# SiP.net
KiCad netlist of a schematic drawn in Altium Designer
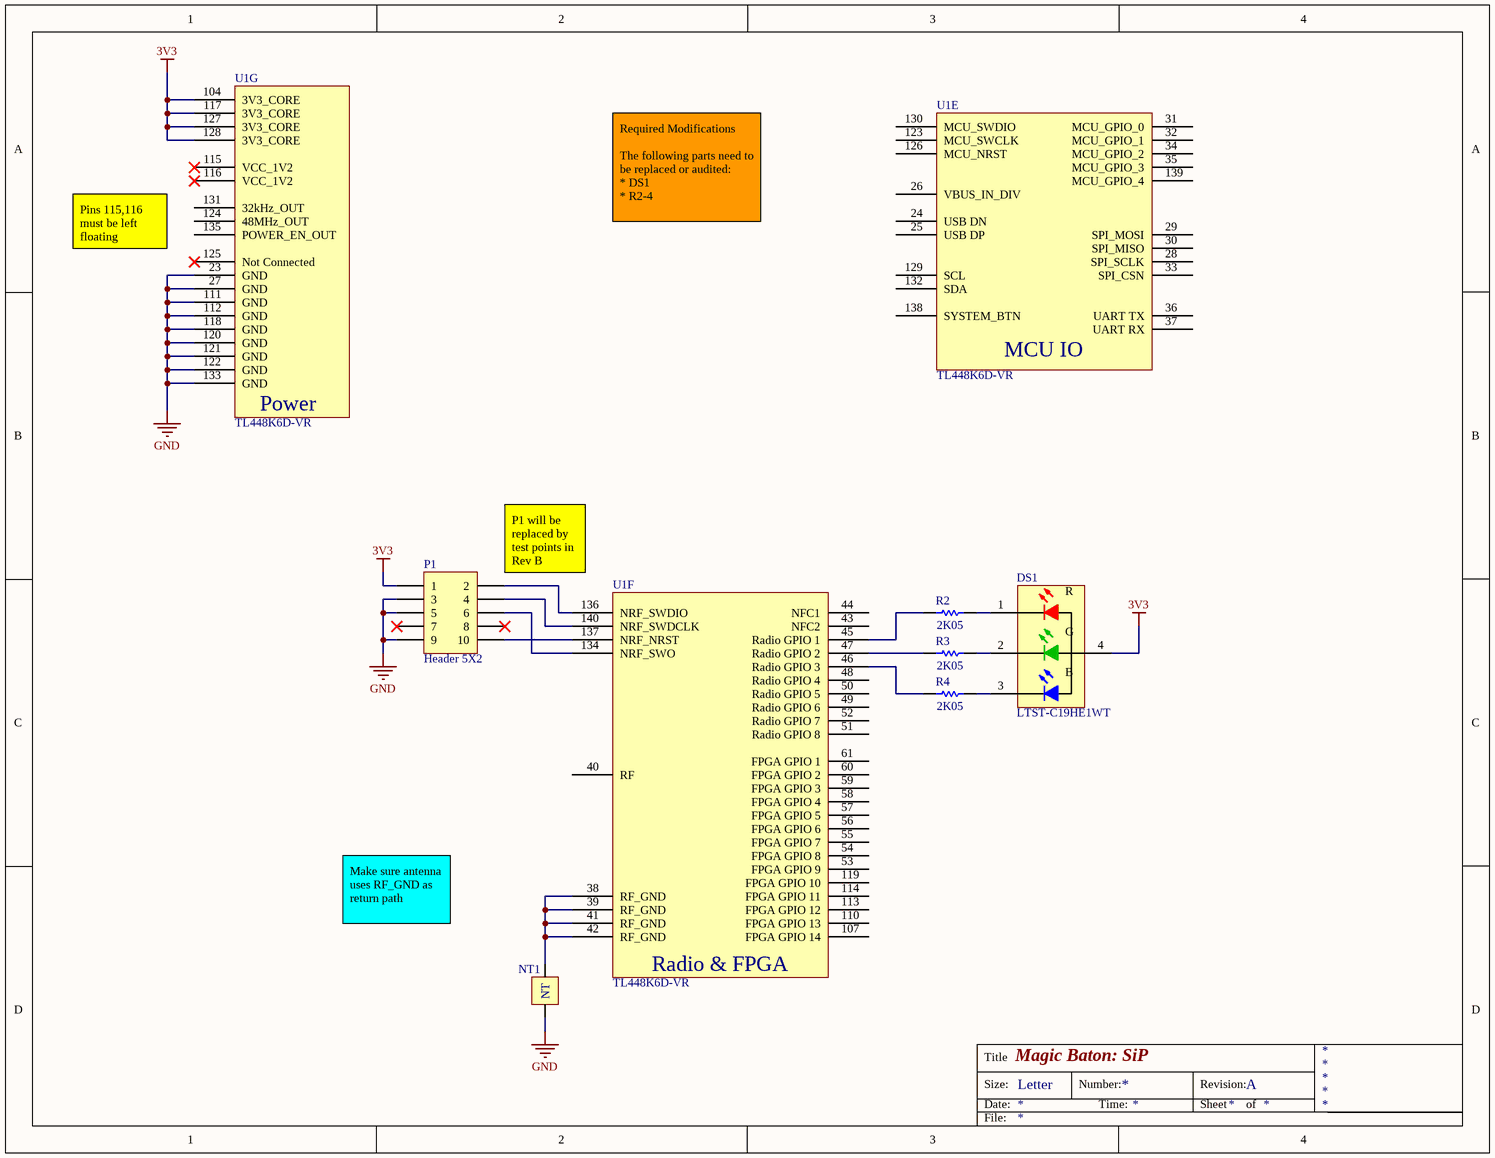
[diagram p0: SiP.SchDoc]

(export (version "E")
  (design (tool "Eeschema 10.0.6"))
  (components
    (comp (ref "DS1")
      (value "LTST-C19HE1WT")
      (footprint "LTST-C19HE1WT-4_V")
      (description "LED Tri-Color Blue/Green/Red, 5 V, -20 to 80 degC, 4-Pin SMD, RoHS, Tape and Reel")
      (fields (field (name "MANUFACTURER") "Lite-On"))
      (libsource (lib "Altium Content Vault") (part "LTST-C19HE1WT-4"))
    )
    (comp (ref "NT1") (value "NT1") (description "Nettie") (libsource (lib "CustomParts") (part "NT1")))
    (comp (ref "P1")
      (value "Header 5X2")
      (footprint "HDR2X5")
      (description "Header, 5-Pin, Dual row")
      (fields (field (name "PUBLISHER") "Altium Limited"))
      (libsource (lib "Miscellaneous Connectors") (part "Header 5X2"))
    )
    (comp (ref "R2")
      (value "2K05")
      (footprint "AXIAL-0.3")
      (description "Resistor")
      (fields (field (name "Comment") "Res1") (field (name "PUBLISHER") "Altium Limited"))
      (libsource (lib "Miscellaneous Devices") (part "Res1"))
    )
    (comp (ref "R3")
      (value "2K05")
      (footprint "AXIAL-0.3")
      (description "Resistor")
      (fields (field (name "Comment") "Res1") (field (name "PUBLISHER") "Altium Limited"))
      (libsource (lib "Miscellaneous Devices") (part "Res1"))
    )
    (comp (ref "R4")
      (value "2K05")
      (footprint "AXIAL-0.3")
      (description "Resistor")
      (fields (field (name "Comment") "Res1") (field (name "PUBLISHER") "Altium Limited"))
      (libsource (lib "Miscellaneous Devices") (part "Res1"))
    )
    (comp (ref "U1")
      (value "TL448K6D-VR")
      (footprint "WatchmanModule_v4")
      (libsource (lib "TL448K6D-VR_library_rev1p2") (part "TL448K6D-VR"))
    )
  )
  (nets
    (net (code "1") (name "3V3") (class "Default")
      (node (ref "DS1") (pin "4") (pinfunction "A_4") (pintype "passive"))
      (node (ref "P1") (pin "1") (pinfunction "1_1") (pintype "passive"))
      (node (ref "U1") (pin "104") (pinfunction "3V3_CORE_104") (pintype "passive"))
      (node (ref "U1") (pin "117") (pinfunction "3V3_CORE_117") (pintype "passive"))
      (node (ref "U1") (pin "127") (pinfunction "3V3_CORE_127") (pintype "passive"))
      (node (ref "U1") (pin "128") (pinfunction "3V3_CORE_128") (pintype "passive"))
    )
    (net (code "2") (name "GND") (class "Default")
      (node (ref "NT1") (pin "1") (pinfunction "1_1") (pintype "passive"))
      (node (ref "P1") (pin "3") (pinfunction "3_3") (pintype "passive"))
      (node (ref "P1") (pin "5") (pinfunction "5_5") (pintype "passive"))
      (node (ref "P1") (pin "9") (pinfunction "9_9") (pintype "passive"))
      (node (ref "U1") (pin "111") (pinfunction "GND_111") (pintype "passive"))
      (node (ref "U1") (pin "112") (pinfunction "GND_112") (pintype "passive"))
      (node (ref "U1") (pin "118") (pinfunction "GND_118") (pintype "passive"))
      (node (ref "U1") (pin "120") (pinfunction "GND_120") (pintype "passive"))
      (node (ref "U1") (pin "121") (pinfunction "GND_121") (pintype "passive"))
      (node (ref "U1") (pin "122") (pinfunction "GND_122") (pintype "passive"))
      (node (ref "U1") (pin "133") (pinfunction "GND_133") (pintype "passive"))
      (node (ref "U1") (pin "23") (pinfunction "GND_23") (pintype "passive"))
      (node (ref "U1") (pin "27") (pinfunction "GND_27") (pintype "passive"))
    )
    (net (code "3") (name "Net-(DS1-B)") (class "Default")
      (node (ref "DS1") (pin "3") (pinfunction "B_3") (pintype "passive"))
      (node (ref "R4") (pin "2") (pinfunction "2_2") (pintype "passive"))
    )
    (net (code "4") (name "Net-(DS1-G)") (class "Default")
      (node (ref "DS1") (pin "2") (pinfunction "G_2") (pintype "passive"))
      (node (ref "R3") (pin "2") (pinfunction "2_2") (pintype "passive"))
    )
    (net (code "5") (name "Net-(DS1-R)") (class "Default")
      (node (ref "DS1") (pin "1") (pinfunction "R_1") (pintype "passive"))
      (node (ref "R2") (pin "2") (pinfunction "2_2") (pintype "passive"))
    )
    (net (code "6") (name "Net-(NT1-Pad2)") (class "Default")
      (node (ref "NT1") (pin "2") (pinfunction "2_2") (pintype "passive"))
      (node (ref "U1") (pin "38") (pinfunction "RF_GND_38") (pintype "passive"))
      (node (ref "U1") (pin "39") (pinfunction "RF_GND_39") (pintype "passive"))
      (node (ref "U1") (pin "41") (pinfunction "RF_GND_41") (pintype "passive"))
      (node (ref "U1") (pin "42") (pinfunction "RF_GND_42") (pintype "passive"))
    )
    (net (code "7") (name "Net-(U1F-NRF_NRST)") (class "Default")
      (node (ref "P1") (pin "10") (pinfunction "10_10") (pintype "passive"))
      (node (ref "U1") (pin "137") (pinfunction "NRF_NRST_137") (pintype "passive"))
    )
    (net (code "8") (name "Net-(U1F-NRF_SWDCLK)") (class "Default")
      (node (ref "P1") (pin "4") (pinfunction "4_4") (pintype "passive"))
      (node (ref "U1") (pin "140") (pinfunction "NRF_SWDCLK_140") (pintype "passive"))
    )
    (net (code "9") (name "Net-(U1F-NRF_SWDIO)") (class "Default")
      (node (ref "P1") (pin "2") (pinfunction "2_2") (pintype "passive"))
      (node (ref "U1") (pin "136") (pinfunction "NRF_SWDIO_136") (pintype "passive"))
    )
    (net (code "10") (name "Net-(U1F-NRF_SWO)") (class "Default")
      (node (ref "P1") (pin "6") (pinfunction "6_6") (pintype "passive"))
      (node (ref "U1") (pin "134") (pinfunction "NRF_SWO_134") (pintype "passive"))
    )
    (net (code "11") (name "Net-(U1F-Radio_GPIO_1)") (class "Default")
      (node (ref "R2") (pin "1") (pinfunction "1_1") (pintype "passive"))
      (node (ref "U1") (pin "45") (pinfunction "Radio_GPIO_1_45") (pintype "passive"))
    )
    (net (code "12") (name "Net-(U1F-Radio_GPIO_2)") (class "Default")
      (node (ref "R3") (pin "1") (pinfunction "1_1") (pintype "passive"))
      (node (ref "U1") (pin "47") (pinfunction "Radio_GPIO_2_47") (pintype "passive"))
    )
    (net (code "13") (name "Net-(U1F-Radio_GPIO_3)") (class "Default")
      (node (ref "R4") (pin "1") (pinfunction "1_1") (pintype "passive"))
      (node (ref "U1") (pin "46") (pinfunction "Radio_GPIO_3_46") (pintype "passive"))
    )
    (net (code "14") (name "unconnected-(P1-Pad7)") (class "Default")
      (node (ref "P1") (pin "7") (pinfunction "7_7") (pintype "passive+no_connect"))
    )
    (net (code "15") (name "unconnected-(P1-Pad8)") (class "Default")
      (node (ref "P1") (pin "8") (pinfunction "8_8") (pintype "passive+no_connect"))
    )
    (net (code "16") (name "unconnected-(U1E-MCU_GPIO_0-Pad31)") (class "Default")
      (node (ref "U1") (pin "31") (pinfunction "MCU_GPIO_0_31") (pintype "passive"))
    )
    (net (code "17") (name "unconnected-(U1E-MCU_GPIO_1-Pad32)") (class "Default")
      (node (ref "U1") (pin "32") (pinfunction "MCU_GPIO_1_32") (pintype "passive"))
    )
    (net (code "18") (name "unconnected-(U1E-MCU_GPIO_2-Pad34)") (class "Default")
      (node (ref "U1") (pin "34") (pinfunction "MCU_GPIO_2_34") (pintype "passive"))
    )
    (net (code "19") (name "unconnected-(U1E-MCU_GPIO_3-Pad35)") (class "Default")
      (node (ref "U1") (pin "35") (pinfunction "MCU_GPIO_3_35") (pintype "passive"))
    )
    (net (code "20") (name "unconnected-(U1E-MCU_GPIO_4-Pad139)") (class "Default")
      (node (ref "U1") (pin "139") (pinfunction "MCU_GPIO_4_139") (pintype "passive"))
    )
    (net (code "21") (name "unconnected-(U1E-MCU_NRST-Pad126)") (class "Default")
      (node (ref "U1") (pin "126") (pinfunction "MCU_NRST_126") (pintype "passive"))
    )
    (net (code "22") (name "unconnected-(U1E-MCU_SWCLK-Pad123)") (class "Default")
      (node (ref "U1") (pin "123") (pinfunction "MCU_SWCLK_123") (pintype "passive"))
    )
    (net (code "23") (name "unconnected-(U1E-MCU_SWDIO-Pad130)") (class "Default")
      (node (ref "U1") (pin "130") (pinfunction "MCU_SWDIO_130") (pintype "passive"))
    )
    (net (code "24") (name "unconnected-(U1E-SCL-Pad129)") (class "Default")
      (node (ref "U1") (pin "129") (pinfunction "SCL_129") (pintype "passive"))
    )
    (net (code "25") (name "unconnected-(U1E-SDA-Pad132)") (class "Default")
      (node (ref "U1") (pin "132") (pinfunction "SDA_132") (pintype "passive"))
    )
    (net (code "26") (name "unconnected-(U1E-SPI_CSN-Pad33)") (class "Default")
      (node (ref "U1") (pin "33") (pinfunction "SPI_CSN_33") (pintype "passive"))
    )
    (net (code "27") (name "unconnected-(U1E-SPI_MISO-Pad30)") (class "Default")
      (node (ref "U1") (pin "30") (pinfunction "SPI_MISO_30") (pintype "passive"))
    )
    (net (code "28") (name "unconnected-(U1E-SPI_MOSI-Pad29)") (class "Default")
      (node (ref "U1") (pin "29") (pinfunction "SPI_MOSI_29") (pintype "passive"))
    )
    (net (code "29") (name "unconnected-(U1E-SPI_SCLK-Pad28)") (class "Default")
      (node (ref "U1") (pin "28") (pinfunction "SPI_SCLK_28") (pintype "passive"))
    )
    (net (code "30") (name "unconnected-(U1E-SYSTEM_BTN-Pad138)") (class "Default")
      (node (ref "U1") (pin "138") (pinfunction "SYSTEM_BTN_138") (pintype "passive"))
    )
    (net (code "31") (name "unconnected-(U1E-UART_RX-Pad37)") (class "Default")
      (node (ref "U1") (pin "37") (pinfunction "UART_RX_37") (pintype "passive"))
    )
    (net (code "32") (name "unconnected-(U1E-UART_TX-Pad36)") (class "Default")
      (node (ref "U1") (pin "36") (pinfunction "UART_TX_36") (pintype "passive"))
    )
    (net (code "33") (name "unconnected-(U1E-USB_DN-Pad24)") (class "Default")
      (node (ref "U1") (pin "24") (pinfunction "USB_DN_24") (pintype "passive"))
    )
    (net (code "34") (name "unconnected-(U1E-USB_DP-Pad25)") (class "Default")
      (node (ref "U1") (pin "25") (pinfunction "USB_DP_25") (pintype "passive"))
    )
    (net (code "35") (name "unconnected-(U1E-VBUS_IN_DIV-Pad26)") (class "Default")
      (node (ref "U1") (pin "26") (pinfunction "VBUS_IN_DIV_26") (pintype "passive"))
    )
    (net (code "36") (name "unconnected-(U1F-FPGA_GPIO_1-Pad61)") (class "Default")
      (node (ref "U1") (pin "61") (pinfunction "FPGA_GPIO_1_61") (pintype "passive"))
    )
    (net (code "37") (name "unconnected-(U1F-FPGA_GPIO_2-Pad60)") (class "Default")
      (node (ref "U1") (pin "60") (pinfunction "FPGA_GPIO_2_60") (pintype "passive"))
    )
    (net (code "38") (name "unconnected-(U1F-FPGA_GPIO_3-Pad59)") (class "Default")
      (node (ref "U1") (pin "59") (pinfunction "FPGA_GPIO_3_59") (pintype "passive"))
    )
    (net (code "39") (name "unconnected-(U1F-FPGA_GPIO_4-Pad58)") (class "Default")
      (node (ref "U1") (pin "58") (pinfunction "FPGA_GPIO_4_58") (pintype "passive"))
    )
    (net (code "40") (name "unconnected-(U1F-FPGA_GPIO_5-Pad57)") (class "Default")
      (node (ref "U1") (pin "57") (pinfunction "FPGA_GPIO_5_57") (pintype "passive"))
    )
    (net (code "41") (name "unconnected-(U1F-FPGA_GPIO_6-Pad56)") (class "Default")
      (node (ref "U1") (pin "56") (pinfunction "FPGA_GPIO_6_56") (pintype "passive"))
    )
    (net (code "42") (name "unconnected-(U1F-FPGA_GPIO_7-Pad55)") (class "Default")
      (node (ref "U1") (pin "55") (pinfunction "FPGA_GPIO_7_55") (pintype "passive"))
    )
    (net (code "43") (name "unconnected-(U1F-FPGA_GPIO_8-Pad54)") (class "Default")
      (node (ref "U1") (pin "54") (pinfunction "FPGA_GPIO_8_54") (pintype "passive"))
    )
    (net (code "44") (name "unconnected-(U1F-FPGA_GPIO_9-Pad53)") (class "Default")
      (node (ref "U1") (pin "53") (pinfunction "FPGA_GPIO_9_53") (pintype "passive"))
    )
    (net (code "45") (name "unconnected-(U1F-FPGA_GPIO_10-Pad119)") (class "Default")
      (node (ref "U1") (pin "119") (pinfunction "FPGA_GPIO_10_119") (pintype "passive"))
    )
    (net (code "46") (name "unconnected-(U1F-FPGA_GPIO_11-Pad114)") (class "Default")
      (node (ref "U1") (pin "114") (pinfunction "FPGA_GPIO_11_114") (pintype "passive"))
    )
    (net (code "47") (name "unconnected-(U1F-FPGA_GPIO_12-Pad113)") (class "Default")
      (node (ref "U1") (pin "113") (pinfunction "FPGA_GPIO_12_113") (pintype "passive"))
    )
    (net (code "48") (name "unconnected-(U1F-FPGA_GPIO_13-Pad110)") (class "Default")
      (node (ref "U1") (pin "110") (pinfunction "FPGA_GPIO_13_110") (pintype "passive"))
    )
    (net (code "49") (name "unconnected-(U1F-FPGA_GPIO_14-Pad107)") (class "Default")
      (node (ref "U1") (pin "107") (pinfunction "FPGA_GPIO_14_107") (pintype "passive"))
    )
    (net (code "50") (name "unconnected-(U1F-NFC1-Pad44)") (class "Default")
      (node (ref "U1") (pin "44") (pinfunction "NFC1_44") (pintype "passive"))
    )
    (net (code "51") (name "unconnected-(U1F-NFC2-Pad43)") (class "Default")
      (node (ref "U1") (pin "43") (pinfunction "NFC2_43") (pintype "passive"))
    )
    (net (code "52") (name "unconnected-(U1F-RF-Pad40)") (class "Default")
      (node (ref "U1") (pin "40") (pinfunction "RF_40") (pintype "passive"))
    )
    (net (code "53") (name "unconnected-(U1F-Radio_GPIO_4-Pad48)") (class "Default")
      (node (ref "U1") (pin "48") (pinfunction "Radio_GPIO_4_48") (pintype "passive"))
    )
    (net (code "54") (name "unconnected-(U1F-Radio_GPIO_5-Pad50)") (class "Default")
      (node (ref "U1") (pin "50") (pinfunction "Radio_GPIO_5_50") (pintype "passive"))
    )
    (net (code "55") (name "unconnected-(U1F-Radio_GPIO_6-Pad49)") (class "Default")
      (node (ref "U1") (pin "49") (pinfunction "Radio_GPIO_6_49") (pintype "passive"))
    )
    (net (code "56") (name "unconnected-(U1F-Radio_GPIO_7-Pad52)") (class "Default")
      (node (ref "U1") (pin "52") (pinfunction "Radio_GPIO_7_52") (pintype "passive"))
    )
    (net (code "57") (name "unconnected-(U1F-Radio_GPIO_8-Pad51)") (class "Default")
      (node (ref "U1") (pin "51") (pinfunction "Radio_GPIO_8_51") (pintype "passive"))
    )
    (net (code "58") (name "unconnected-(U1G-32kHz_OUT-Pad131)") (class "Default")
      (node (ref "U1") (pin "131") (pinfunction "32kHz_OUT_131") (pintype "passive"))
    )
    (net (code "59") (name "unconnected-(U1G-48MHz_OUT-Pad124)") (class "Default")
      (node (ref "U1") (pin "124") (pinfunction "48MHz_OUT_124") (pintype "passive"))
    )
    (net (code "60") (name "unconnected-(U1G-Not_Connected-Pad125)") (class "Default")
      (node (ref "U1") (pin "125") (pinfunction "Not_Connected_125") (pintype "passive+no_connect"))
    )
    (net (code "61") (name "unconnected-(U1G-POWER_EN_OUT-Pad135)") (class "Default")
      (node (ref "U1") (pin "135") (pinfunction "POWER_EN_OUT_135") (pintype "passive"))
    )
    (net (code "62") (name "unconnected-(U1G-VCC_1V2-Pad115)") (class "Default")
      (node (ref "U1") (pin "115") (pinfunction "VCC_1V2_115") (pintype "passive+no_connect"))
    )
    (net (code "63") (name "unconnected-(U1G-VCC_1V2-Pad116)") (class "Default")
      (node (ref "U1") (pin "116") (pinfunction "VCC_1V2_116") (pintype "passive+no_connect"))
    )
  )
)
